# Battery_Monitoring.net
KiCad netlist of a schematic drawn in Altium Designer
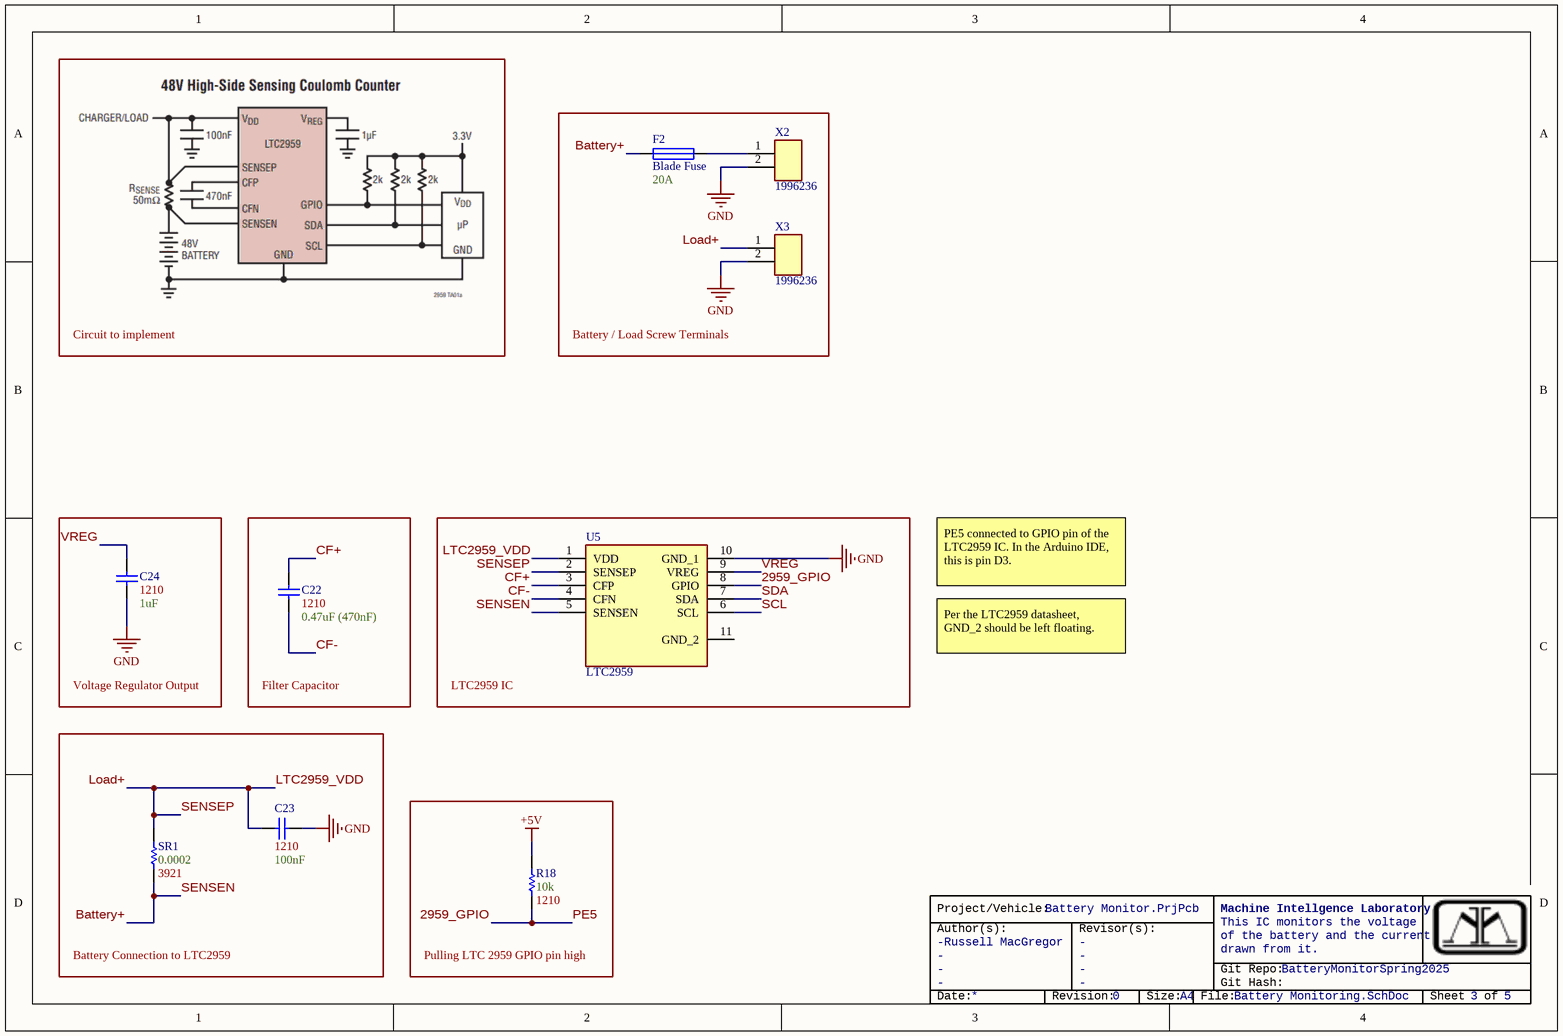
[diagram p0: Battery Monitoring.SchDoc]

(export (version "E")
  (design (tool "Eeschema 10.0.6"))
  (components
    (comp (ref "C22")
      (value "SMD Cap - Nonpolarized")
      (footprint "SMD Capacitor [1210]")
      (fields
        (field (name "MOUSER PART #") "80-C1210C474K1RAUTO")
        (field (name "SIZE PACKAGE") "1210")
        (field (name "CAPACITANCE") "0.47uF (470nF)")
      )
      (libsource (lib "RADM Components") (part "SMD Cap - Nonpolarized"))
    )
    (comp (ref "C23")
      (value "SMD Cap - Nonpolarized")
      (footprint "SMD Capacitor [1210]")
      (fields
        (field (name "MOUSER PART #") "581-12107C104KAT2A")
        (field (name "SIZE PACKAGE") "1210")
        (field (name "CAPACITANCE") "100nF")
      )
      (libsource (lib "RADM Components") (part "SMD Cap - Nonpolarized"))
    )
    (comp (ref "C24")
      (value "SMD Cap - Nonpolarized")
      (footprint "SMD Capacitor [1210]")
      (fields
        (field (name "MOUSER PART #") "80-C1210X105K5RAUTO")
        (field (name "SIZE PACKAGE") "1210")
        (field (name "CAPACITANCE") "1uF")
      )
      (libsource (lib "RADM Components") (part "SMD Cap - Nonpolarized"))
    )
    (comp (ref "F2")
      (value "Blade Fuse")
      (footprint "Blade Fuse [2]")
      (description "Standard Fuse Socket")
      (fields (field (name "MOUSER PART #") "576-178.6165.0002") (field (name "CAPACITY") "20A"))
      (libsource (lib "RADM Components") (part "Blade Fuse"))
    )
    (comp (ref "R18")
      (value "SMD Resistor")
      (footprint "SMD Resistor [1210]")
      (description "JLC Part #: C728401\r\n(for 1M Ohm Res)")
      (fields
        (field (name "MOUSER PART #") "71-CRCW121010K0JNAIF")
        (field (name "RESISTANCE") "10k")
        (field (name "SIZE PACKAGE") "1210")
      )
      (libsource (lib "RADM Components") (part "SMD Resistor"))
    )
    (comp (ref "SR1")
      (value "SMD Resistor")
      (footprint "SMD Resistor [3921]")
      (fields
        (field (name "JLC PART #") "C728401")
        (field (name "MOUSER PART #") "71-WSL3921L2000FEA")
        (field (name "RESISTANCE") "0.0002")
        (field (name "SIZE PACKAGE") "3921")
      )
      (libsource (lib "RADM Components") (part "SMD Resistor"))
    )
    (comp (ref "U5")
      (value "LTC2959")
      (footprint "Battery Monitor IC")
      (fields (field (name "MOUSER PART #") "584-LTC2959IDDBTRMPB"))
      (libsource (lib "RADM Components") (part "LTC2959 Battery Monitor IC"))
    )
    (comp (ref "X2")
      (value "1996236")
      (footprint "Screw Terminal [1996236]")
      (fields (field (name "MOUSER PART #") "651-1996236"))
      (libsource (lib "RADM Components") (part "Screw Terminal [1996236]"))
    )
    (comp (ref "X3")
      (value "1996236")
      (footprint "Screw Terminal [1996236]")
      (fields (field (name "MOUSER PART #") "651-1996236"))
      (libsource (lib "RADM Components") (part "Screw Terminal [1996236]"))
    )
  )
  (nets
    (net (code "1") (name "+5V") (class "Default")
      (node (ref "R18") (pin "1") (pinfunction "1_1") (pintype "passive"))
    )
    (net (code "2") (name "/2959_GPIO") (class "Default")
      (node (ref "R18") (pin "2") (pinfunction "2_2") (pintype "passive"))
      (node (ref "U5") (pin "8") (pinfunction "GPIO_8") (pintype "passive"))
    )
    (net (code "3") (name "/Battery+") (class "Default")
      (node (ref "F2") (pin "1") (pinfunction "1_1") (pintype "passive"))
      (node (ref "SR1") (pin "1") (pinfunction "1_1") (pintype "passive"))
      (node (ref "U5") (pin "5") (pinfunction "SENSEN_5") (pintype "passive"))
    )
    (net (code "4") (name "/CF+") (class "Default")
      (node (ref "C22") (pin "1") (pinfunction "1_1") (pintype "passive"))
      (node (ref "U5") (pin "3") (pinfunction "CFP_3") (pintype "passive"))
    )
    (net (code "5") (name "/CF-") (class "Default")
      (node (ref "C22") (pin "2") (pinfunction "2_2") (pintype "passive"))
      (node (ref "U5") (pin "4") (pinfunction "CFN_4") (pintype "passive"))
    )
    (net (code "6") (name "/LTC2959_VDD") (class "Default")
      (node (ref "C23") (pin "2") (pinfunction "2_2") (pintype "passive"))
      (node (ref "SR1") (pin "2") (pinfunction "2_2") (pintype "passive"))
      (node (ref "U5") (pin "1") (pinfunction "VDD_1") (pintype "passive"))
      (node (ref "U5") (pin "2") (pinfunction "SENSEP_2") (pintype "passive"))
      (node (ref "X3") (pin "1") (pintype "passive"))
    )
    (net (code "7") (name "/SCL") (class "Default")
      (node (ref "U5") (pin "6") (pinfunction "SCL_6") (pintype "passive"))
    )
    (net (code "8") (name "/SDA") (class "Default")
      (node (ref "U5") (pin "7") (pinfunction "SDA_7") (pintype "passive"))
    )
    (net (code "9") (name "/VREG") (class "Default")
      (node (ref "C24") (pin "1") (pinfunction "1_1") (pintype "passive"))
      (node (ref "U5") (pin "9") (pinfunction "VREG_9") (pintype "passive"))
    )
    (net (code "10") (name "GND") (class "Default")
      (node (ref "C23") (pin "1") (pinfunction "1_1") (pintype "passive"))
      (node (ref "C24") (pin "2") (pinfunction "2_2") (pintype "passive"))
      (node (ref "U5") (pin "10") (pinfunction "GND_1_10") (pintype "passive"))
      (node (ref "X2") (pin "2") (pinfunction "2_2") (pintype "passive"))
      (node (ref "X3") (pin "2") (pinfunction "2_2") (pintype "passive"))
    )
    (net (code "11") (name "Net-(F2-Pad2)") (class "Default")
      (node (ref "F2") (pin "2") (pinfunction "2_2") (pintype "passive"))
      (node (ref "X2") (pin "1") (pintype "passive"))
    )
    (net (code "12") (name "unconnected-(U5-GND_2-Pad11)") (class "Default")
      (node (ref "U5") (pin "11") (pinfunction "GND_2_11") (pintype "passive"))
    )
  )
)
